# PPM2DSM_fix.net
KiCad netlist of a schematic drawn in EAGLE
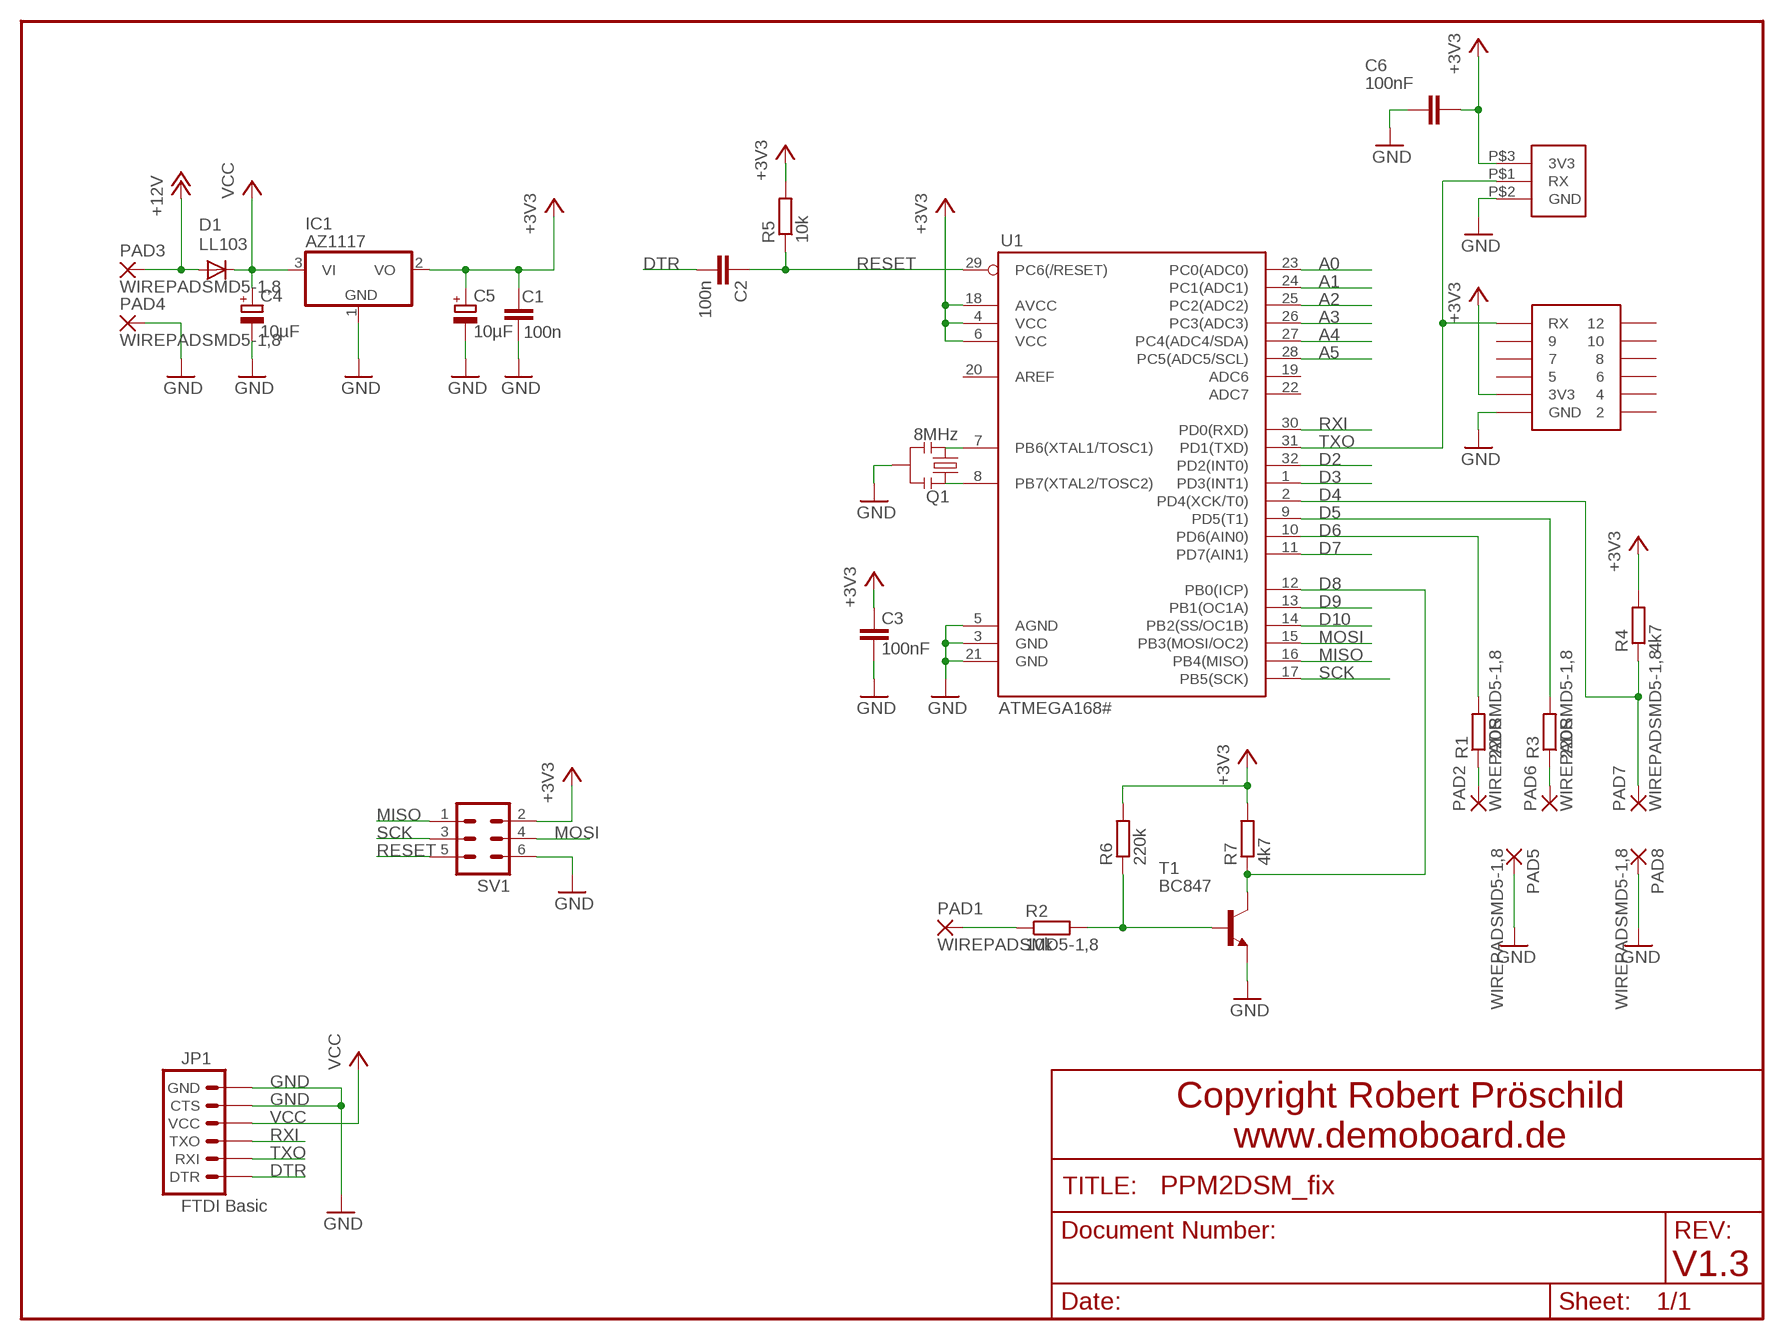
[diagram p0: schematic, sheet 1]

(export (version "E")
  (design (tool "Eeschema 10.0.6"))
  (components
    (comp (ref "C1")
      (value "100n")
      (footprint "eagle-import:C0805")
      (libsource (lib "eagle-import") (part "C-EUC0805"))
    )
    (comp (ref "C2")
      (value "100n")
      (footprint "eagle-import:C0805")
      (libsource (lib "eagle-import") (part "C-EUC0805"))
    )
    (comp (ref "C3")
      (value "100nF")
      (footprint "eagle-import:C0805")
      (libsource (lib "eagle-import") (part "C-EUC0805"))
    )
    (comp (ref "C4")
      (value "10µF")
      (footprint "eagle-import:CT6032")
      (libsource (lib "eagle-import") (part "CPOL-EUCT6032"))
    )
    (comp (ref "C5")
      (value "10µF")
      (footprint "eagle-import:CT6032")
      (libsource (lib "eagle-import") (part "CPOL-EUCT6032"))
    )
    (comp (ref "C6")
      (value "100nF")
      (footprint "eagle-import:C0805")
      (libsource (lib "eagle-import") (part "C-EUC0805"))
    )
    (comp (ref "D1")
      (value "LL103")
      (footprint "eagle-import:MINIMELF")
      (libsource (lib "eagle-import") (part "DIODE-MINIMELF"))
    )
    (comp (ref "IC1")
      (value "AZ1117")
      (footprint "eagle-import:SOT223")
      (libsource (lib "eagle-import") (part "AZ1117"))
    )
    (comp (ref "IC2")
      (value "X10EMTX")
      (footprint "eagle-import:X10EMTX")
      (libsource (lib "eagle-import") (part "X10EMTX"))
    )
    (comp (ref "IC3")
      (value "X1TX0")
      (footprint "eagle-import:X1TX0")
      (libsource (lib "eagle-import") (part "X1TX0"))
    )
    (comp (ref "JP1")
      (value "FTDI Basic")
      (footprint "eagle-import:1X06")
      (libsource (lib "eagle-import") (part "ARDUINO_SERIAL_PROGRAMPTH"))
    )
    (comp (ref "PAD1")
      (value "WIREPADSMD5-1,8")
      (footprint "eagle-import:5-1,8")
      (libsource (lib "eagle-import") (part "WIREPADSMD5-1,8"))
    )
    (comp (ref "PAD2")
      (value "WIREPADSMD5-1,8")
      (footprint "eagle-import:5-1,8")
      (libsource (lib "eagle-import") (part "WIREPADSMD5-1,8"))
    )
    (comp (ref "PAD3")
      (value "WIREPADSMD5-1,8")
      (footprint "eagle-import:5-1,8")
      (libsource (lib "eagle-import") (part "WIREPADSMD5-1,8"))
    )
    (comp (ref "PAD4")
      (value "WIREPADSMD5-1,8")
      (footprint "eagle-import:5-1,8")
      (libsource (lib "eagle-import") (part "WIREPADSMD5-1,8"))
    )
    (comp (ref "PAD5")
      (value "WIREPADSMD5-1,8")
      (footprint "eagle-import:5-1,8")
      (libsource (lib "eagle-import") (part "WIREPADSMD5-1,8"))
    )
    (comp (ref "PAD6")
      (value "WIREPADSMD5-1,8")
      (footprint "eagle-import:5-1,8")
      (libsource (lib "eagle-import") (part "WIREPADSMD5-1,8"))
    )
    (comp (ref "PAD7")
      (value "WIREPADSMD5-1,8")
      (footprint "eagle-import:5-1,8")
      (libsource (lib "eagle-import") (part "WIREPADSMD5-1,8"))
    )
    (comp (ref "PAD8")
      (value "WIREPADSMD5-1,8")
      (footprint "eagle-import:5-1,8")
      (libsource (lib "eagle-import") (part "WIREPADSMD5-1,8"))
    )
    (comp (ref "Q1")
      (value "8MHz")
      (footprint "eagle-import:RESONATOR-SMD")
      (libsource (lib "eagle-import") (part "RESONATORSMD"))
    )
    (comp (ref "R1")
      (value "220R")
      (footprint "eagle-import:R0805")
      (libsource (lib "eagle-import") (part "R-EU_R0805"))
    )
    (comp (ref "R2")
      (value "10k")
      (footprint "eagle-import:R0805")
      (libsource (lib "eagle-import") (part "R-EU_R0805"))
    )
    (comp (ref "R3")
      (value "220R")
      (footprint "eagle-import:R0805")
      (libsource (lib "eagle-import") (part "R-EU_R0805"))
    )
    (comp (ref "R4")
      (value "4k7")
      (footprint "eagle-import:R0805")
      (libsource (lib "eagle-import") (part "R-EU_R0805"))
    )
    (comp (ref "R5")
      (value "10k")
      (footprint "eagle-import:R0805")
      (libsource (lib "eagle-import") (part "R-EU_R0805"))
    )
    (comp (ref "R6")
      (value "220k")
      (footprint "eagle-import:R0805")
      (libsource (lib "eagle-import") (part "R-EU_R0805"))
    )
    (comp (ref "R7")
      (value "4k7")
      (footprint "eagle-import:R0805")
      (libsource (lib "eagle-import") (part "R-EU_R0805"))
    )
    (comp (ref "SV1")
      (value "MA03-2")
      (footprint "eagle-import:MA03-2")
      (libsource (lib "eagle-import") (part "MA03-2"))
    )
    (comp (ref "T1")
      (value "BC847")
      (footprint "eagle-import:SOT23")
      (libsource (lib "eagle-import") (part "BC847"))
    )
    (comp (ref "U1")
      (value "ATMEGA168#")
      (footprint "eagle-import:TQFP32-08")
      (libsource (lib "eagle-import") (part "ATMEGA168"))
    )
  )
  (nets
    (net (code "1") (name "+3V3") (class "Default")
      (node (ref "C1") (pin "2") (pinfunction "2_2") (pintype "passive"))
      (node (ref "C3") (pin "2") (pinfunction "2_2") (pintype "passive"))
      (node (ref "C5") (pin "+") (pinfunction "+_+") (pintype "passive"))
      (node (ref "C6") (pin "2") (pinfunction "2_2") (pintype "passive"))
      (node (ref "IC1") (pin "2") (pinfunction "VO_2") (pintype "passive"))
      (node (ref "IC2") (pin "P$3") (pinfunction "3V3_P$3") (pintype "power_in"))
      (node (ref "IC3") (pin "3") (pinfunction "3V3_3") (pintype "bidirectional"))
      (node (ref "R4") (pin "2") (pinfunction "2_2") (pintype "passive"))
      (node (ref "R5") (pin "2") (pinfunction "2_2") (pintype "passive"))
      (node (ref "R6") (pin "2") (pinfunction "2_2") (pintype "passive"))
      (node (ref "R7") (pin "2") (pinfunction "2_2") (pintype "passive"))
      (node (ref "SV1") (pin "2") (pinfunction "2_2") (pintype "passive"))
      (node (ref "U1") (pin "18") (pinfunction "AVCC_18") (pintype "bidirectional"))
      (node (ref "U1") (pin "4") (pinfunction "VCC_4") (pintype "bidirectional"))
      (node (ref "U1") (pin "6") (pinfunction "VCC_6") (pintype "bidirectional"))
    )
    (net (code "2") (name "+12V") (class "Default")
      (node (ref "D1") (pin "A") (pinfunction "A_A") (pintype "passive"))
      (node (ref "PAD3") (pin "1") (pinfunction "P_1") (pintype "passive"))
    )
    (net (code "3") (name "/2") (class "Default")
      (node (ref "IC3") (pin "2") (pinfunction "2_2") (pintype "power_in"))
    )
    (net (code "4") (name "/4") (class "Default")
      (node (ref "IC3") (pin "4") (pinfunction "4_4") (pintype "power_in"))
    )
    (net (code "5") (name "/A0") (class "Default")
      (node (ref "U1") (pin "23") (pinfunction "PC0(ADC0)_23") (pintype "bidirectional"))
    )
    (net (code "6") (name "/A1") (class "Default")
      (node (ref "U1") (pin "24") (pinfunction "PC1(ADC1)_24") (pintype "bidirectional"))
    )
    (net (code "7") (name "/A2") (class "Default")
      (node (ref "U1") (pin "25") (pinfunction "PC2(ADC2)_25") (pintype "bidirectional"))
    )
    (net (code "8") (name "/A3") (class "Default")
      (node (ref "U1") (pin "26") (pinfunction "PC3(ADC3)_26") (pintype "bidirectional"))
    )
    (net (code "9") (name "/A4") (class "Default")
      (node (ref "U1") (pin "27") (pinfunction "PC4(ADC4/SDA)_27") (pintype "bidirectional"))
    )
    (net (code "10") (name "/A5") (class "Default")
      (node (ref "U1") (pin "28") (pinfunction "PC5(ADC5/SCL)_28") (pintype "bidirectional"))
    )
    (net (code "11") (name "/D2") (class "Default")
      (node (ref "U1") (pin "32") (pinfunction "PD2(INT0)_32") (pintype "bidirectional"))
    )
    (net (code "12") (name "/D3") (class "Default")
      (node (ref "U1") (pin "1") (pinfunction "PD3(INT1)_1") (pintype "bidirectional"))
    )
    (net (code "13") (name "/D4") (class "Default")
      (node (ref "PAD7") (pin "1") (pinfunction "P_1") (pintype "passive"))
      (node (ref "R4") (pin "1") (pinfunction "1_1") (pintype "passive"))
      (node (ref "U1") (pin "2") (pinfunction "PD4(XCK/T0)_2") (pintype "bidirectional"))
    )
    (net (code "14") (name "/D5") (class "Default")
      (node (ref "R3") (pin "2") (pinfunction "2_2") (pintype "passive"))
      (node (ref "U1") (pin "9") (pinfunction "PD5(T1)_9") (pintype "bidirectional"))
    )
    (net (code "15") (name "/D6") (class "Default")
      (node (ref "R1") (pin "2") (pinfunction "2_2") (pintype "passive"))
      (node (ref "U1") (pin "10") (pinfunction "PD6(AIN0)_10") (pintype "bidirectional"))
    )
    (net (code "16") (name "/D7") (class "Default")
      (node (ref "U1") (pin "11") (pinfunction "PD7(AIN1)_11") (pintype "bidirectional"))
    )
    (net (code "17") (name "/D8") (class "Default")
      (node (ref "R7") (pin "1") (pinfunction "1_1") (pintype "passive"))
      (node (ref "T1") (pin "3") (pinfunction "C_3") (pintype "passive"))
      (node (ref "U1") (pin "12") (pinfunction "PB0(ICP)_12") (pintype "bidirectional"))
    )
    (net (code "18") (name "/D9") (class "Default")
      (node (ref "U1") (pin "13") (pinfunction "PB1(OC1A)_13") (pintype "bidirectional"))
    )
    (net (code "19") (name "/D10") (class "Default")
      (node (ref "U1") (pin "14") (pinfunction "PB2(SS/OC1B)_14") (pintype "bidirectional"))
    )
    (net (code "20") (name "/DTR") (class "Default")
      (node (ref "C2") (pin "2") (pinfunction "2_2") (pintype "passive"))
      (node (ref "JP1") (pin "1") (pinfunction "DTR_1") (pintype "passive"))
    )
    (net (code "21") (name "/MISO") (class "Default")
      (node (ref "SV1") (pin "1") (pinfunction "1_1") (pintype "passive"))
      (node (ref "U1") (pin "16") (pinfunction "PB4(MISO)_16") (pintype "bidirectional"))
    )
    (net (code "22") (name "/MOSI") (class "Default")
      (node (ref "SV1") (pin "4") (pinfunction "4_4") (pintype "passive"))
      (node (ref "U1") (pin "15") (pinfunction "PB3(MOSI/OC2)_15") (pintype "bidirectional"))
    )
    (net (code "23") (name "/RESET") (class "Default")
      (node (ref "C2") (pin "1") (pinfunction "1_1") (pintype "passive"))
      (node (ref "R5") (pin "1") (pinfunction "1_1") (pintype "passive"))
      (node (ref "SV1") (pin "5") (pinfunction "5_5") (pintype "passive"))
      (node (ref "U1") (pin "29") (pinfunction "PC6(/RESET)_29") (pintype "bidirectional"))
    )
    (net (code "24") (name "/RXI") (class "Default")
      (node (ref "JP1") (pin "3") (pinfunction "TXO_3") (pintype "passive"))
      (node (ref "U1") (pin "30") (pinfunction "PD0(RXD)_30") (pintype "bidirectional"))
    )
    (net (code "25") (name "/SCK") (class "Default")
      (node (ref "SV1") (pin "3") (pinfunction "3_3") (pintype "passive"))
      (node (ref "U1") (pin "17") (pinfunction "PB5(SCK)_17") (pintype "bidirectional"))
    )
    (net (code "26") (name "/TXO") (class "Default")
      (node (ref "IC2") (pin "P$1") (pinfunction "RX_P$1") (pintype "input"))
      (node (ref "IC3") (pin "11") (pinfunction "RX_11") (pintype "bidirectional"))
      (node (ref "JP1") (pin "2") (pinfunction "RXI_2") (pintype "passive"))
      (node (ref "U1") (pin "31") (pinfunction "PD1(TXD)_31") (pintype "bidirectional"))
    )
    (net (code "27") (name "GND") (class "Default")
      (node (ref "C1") (pin "1") (pinfunction "1_1") (pintype "passive"))
      (node (ref "C3") (pin "1") (pinfunction "1_1") (pintype "passive"))
      (node (ref "C4") (pin "-") (pinfunction "-_-") (pintype "passive"))
      (node (ref "C5") (pin "-") (pinfunction "-_-") (pintype "passive"))
      (node (ref "C6") (pin "1") (pinfunction "1_1") (pintype "passive"))
      (node (ref "IC1") (pin "1") (pinfunction "GND_1") (pintype "passive"))
      (node (ref "IC2") (pin "P$2") (pinfunction "GND_P$2") (pintype "power_in"))
      (node (ref "IC3") (pin "1") (pinfunction "GND_1") (pintype "bidirectional"))
      (node (ref "JP1") (pin "5") (pinfunction "CTS_5") (pintype "passive"))
      (node (ref "JP1") (pin "6") (pinfunction "GND_6") (pintype "passive"))
      (node (ref "PAD4") (pin "1") (pinfunction "P_1") (pintype "passive"))
      (node (ref "PAD5") (pin "1") (pinfunction "P_1") (pintype "passive"))
      (node (ref "PAD8") (pin "1") (pinfunction "P_1") (pintype "passive"))
      (node (ref "Q1") (pin "2") (pinfunction "2_2") (pintype "passive"))
      (node (ref "SV1") (pin "6") (pinfunction "6_6") (pintype "passive"))
      (node (ref "T1") (pin "2") (pinfunction "E_2") (pintype "passive"))
      (node (ref "U1") (pin "21") (pinfunction "GND_21") (pintype "bidirectional"))
      (node (ref "U1") (pin "3") (pinfunction "GND_3") (pintype "bidirectional"))
      (node (ref "U1") (pin "5") (pinfunction "AGND_5") (pintype "bidirectional"))
    )
    (net (code "28") (name "Net-(PAD1-P)") (class "Default")
      (node (ref "PAD1") (pin "1") (pinfunction "P_1") (pintype "passive"))
      (node (ref "R2") (pin "1") (pinfunction "1_1") (pintype "passive"))
    )
    (net (code "29") (name "Net-(PAD2-P)") (class "Default")
      (node (ref "PAD2") (pin "1") (pinfunction "P_1") (pintype "passive"))
      (node (ref "R1") (pin "1") (pinfunction "1_1") (pintype "passive"))
    )
    (net (code "30") (name "Net-(PAD6-P)") (class "Default")
      (node (ref "PAD6") (pin "1") (pinfunction "P_1") (pintype "passive"))
      (node (ref "R3") (pin "1") (pinfunction "1_1") (pintype "passive"))
    )
    (net (code "31") (name "Net-(T1-B)") (class "Default")
      (node (ref "R2") (pin "2") (pinfunction "2_2") (pintype "passive"))
      (node (ref "R6") (pin "1") (pinfunction "1_1") (pintype "passive"))
      (node (ref "T1") (pin "1") (pinfunction "B_1") (pintype "passive"))
    )
    (net (code "32") (name "Net-(U1-PB6(XTAL1{slash}TOSC1))") (class "Default")
      (node (ref "Q1") (pin "3") (pinfunction "3_3") (pintype "passive"))
      (node (ref "U1") (pin "7") (pinfunction "PB6(XTAL1/TOSC1)_7") (pintype "bidirectional"))
    )
    (net (code "33") (name "Net-(U1-PB7(XTAL2{slash}TOSC2))") (class "Default")
      (node (ref "Q1") (pin "1") (pinfunction "1_1") (pintype "passive"))
      (node (ref "U1") (pin "8") (pinfunction "PB7(XTAL2/TOSC2)_8") (pintype "bidirectional"))
    )
    (net (code "34") (name "VCC") (class "Default")
      (node (ref "C4") (pin "+") (pinfunction "+_+") (pintype "passive"))
      (node (ref "D1") (pin "C") (pinfunction "C_C") (pintype "passive"))
      (node (ref "IC1") (pin "3") (pinfunction "VI_3") (pintype "input"))
      (node (ref "JP1") (pin "4") (pinfunction "VCC_4") (pintype "passive"))
    )
    (net (code "35") (name "unconnected-(IC3-Pad5)") (class "Default")
      (node (ref "IC3") (pin "5") (pinfunction "5_5") (pintype "bidirectional"))
    )
    (net (code "36") (name "unconnected-(IC3-Pad6)") (class "Default")
      (node (ref "IC3") (pin "6") (pinfunction "6_6") (pintype "bidirectional"))
    )
    (net (code "37") (name "unconnected-(IC3-Pad7)") (class "Default")
      (node (ref "IC3") (pin "7") (pinfunction "7_7") (pintype "bidirectional"))
    )
    (net (code "38") (name "unconnected-(IC3-Pad8)") (class "Default")
      (node (ref "IC3") (pin "8") (pinfunction "8_8") (pintype "bidirectional"))
    )
    (net (code "39") (name "unconnected-(IC3-Pad9)") (class "Default")
      (node (ref "IC3") (pin "9") (pinfunction "9_9") (pintype "bidirectional"))
    )
    (net (code "40") (name "unconnected-(IC3-Pad10)") (class "Default")
      (node (ref "IC3") (pin "10") (pinfunction "10_10") (pintype "bidirectional"))
    )
    (net (code "41") (name "unconnected-(IC3-Pad12)") (class "Default")
      (node (ref "IC3") (pin "12") (pinfunction "12_12") (pintype "input"))
    )
    (net (code "42") (name "unconnected-(U1-ADC6-Pad19)") (class "Default")
      (node (ref "U1") (pin "19") (pinfunction "ADC6_19") (pintype "bidirectional"))
    )
    (net (code "43") (name "unconnected-(U1-ADC7-Pad22)") (class "Default")
      (node (ref "U1") (pin "22") (pinfunction "ADC7_22") (pintype "bidirectional"))
    )
    (net (code "44") (name "unconnected-(U1-AREF-Pad20)") (class "Default")
      (node (ref "U1") (pin "20") (pinfunction "AREF_20") (pintype "bidirectional"))
    )
  )
)
